# t10_arduino_prog.net
KiCad netlist of a schematic drawn in EAGLE
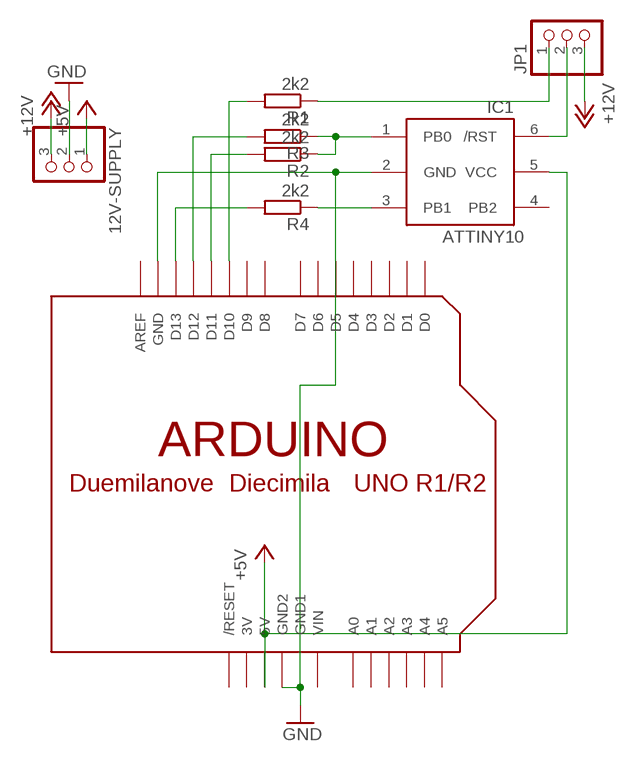
[diagram p0: schematic, sheet 1]

(export (version "E")
  (design (tool "Eeschema 10.0.6"))
  (components
    (comp (ref "12V-SUPPLY")
      (value "PINHD-1X3/90")
      (footprint "eagle-import:1X03_90")
      (libsource (lib "eagle-import") (part "PINHD-1X3/90"))
    )
    (comp (ref "IC1")
      (value "ATTINY10")
      (footprint "eagle-import:SOT23-6")
      (libsource (lib "eagle-import") (part "ATTINY10"))
    )
    (comp (ref "JP1")
      (value "PINHD-1X3")
      (footprint "eagle-import:1X03")
      (libsource (lib "eagle-import") (part "PINHD-1X3"))
    )
    (comp (ref "R1")
      (value "2k2")
      (footprint "eagle-import:0207_2V")
      (libsource (lib "eagle-import") (part "R-EU_0207/2V"))
    )
    (comp (ref "R2")
      (value "2k2")
      (footprint "eagle-import:0207_2V")
      (libsource (lib "eagle-import") (part "R-EU_0207/2V"))
    )
    (comp (ref "R3")
      (value "2k2")
      (footprint "eagle-import:0207_2V")
      (libsource (lib "eagle-import") (part "R-EU_0207/2V"))
    )
    (comp (ref "R4")
      (value "2k2")
      (footprint "eagle-import:0207_2V")
      (libsource (lib "eagle-import") (part "R-EU_0207/2V"))
    )
    (comp (ref "U$1")
      (value "ARDUINO-NOHOLE")
      (footprint "eagle-import:ARDUINO-NOHOLE")
      (libsource (lib "eagle-import") (part "ARDUINO-NOHOLE"))
    )
  )
  (nets
    (net (code "1") (name "+5V") (class "Default")
      (node (ref "12V-SUPPLY") (pin "1") (pinfunction "1_1") (pintype "passive"))
      (node (ref "IC1") (pin "5") (pinfunction "VCC_5") (pintype "power_in"))
      (node (ref "U$1") (pin "5V") (pinfunction "5V_5V") (pintype "power_in"))
    )
    (net (code "2") (name "+12V") (class "Default")
      (node (ref "12V-SUPPLY") (pin "3") (pinfunction "3_3") (pintype "passive"))
      (node (ref "JP1") (pin "3") (pinfunction "3_3") (pintype "passive"))
    )
    (net (code "3") (name "/3V") (class "Default")
      (node (ref "U$1") (pin "3V") (pinfunction "3V_3V") (pintype "power_in"))
    )
    (net (code "4") (name "/VIN") (class "Default")
      (node (ref "U$1") (pin "VIN") (pinfunction "VIN_VIN") (pintype "power_in"))
    )
    (net (code "5") (name "GND") (class "Default")
      (node (ref "12V-SUPPLY") (pin "2") (pinfunction "2_2") (pintype "passive"))
      (node (ref "IC1") (pin "2") (pinfunction "GND_2") (pintype "power_in"))
      (node (ref "U$1") (pin "GND") (pinfunction "GND_GND") (pintype "power_in"))
      (node (ref "U$1") (pin "GND1") (pinfunction "GND1_GND1") (pintype "power_in"))
      (node (ref "U$1") (pin "GND2") (pinfunction "GND2_GND2") (pintype "power_in"))
    )
    (net (code "6") (name "Net-(IC1-PB0)") (class "Default")
      (node (ref "IC1") (pin "1") (pinfunction "PB0_1") (pintype "bidirectional"))
      (node (ref "R2") (pin "1") (pinfunction "1_1") (pintype "passive"))
      (node (ref "R3") (pin "1") (pinfunction "1_1") (pintype "passive"))
    )
    (net (code "7") (name "Net-(IC1-PB1)") (class "Default")
      (node (ref "IC1") (pin "3") (pinfunction "PB1_3") (pintype "bidirectional"))
      (node (ref "R4") (pin "1") (pinfunction "1_1") (pintype "passive"))
    )
    (net (code "8") (name "Net-(IC1-{slash}RST)") (class "Default")
      (node (ref "IC1") (pin "6") (pinfunction "/RST_6") (pintype "bidirectional"))
      (node (ref "JP1") (pin "2") (pinfunction "2_2") (pintype "passive"))
    )
    (net (code "9") (name "Net-(JP1-Pad1)") (class "Default")
      (node (ref "JP1") (pin "1") (pinfunction "1_1") (pintype "passive"))
      (node (ref "R1") (pin "1") (pinfunction "1_1") (pintype "passive"))
    )
    (net (code "10") (name "Net-(R1-Pad2)") (class "Default")
      (node (ref "R1") (pin "2") (pinfunction "2_2") (pintype "passive"))
      (node (ref "U$1") (pin "D10") (pinfunction "D10_D10") (pintype "bidirectional"))
    )
    (net (code "11") (name "Net-(R2-Pad2)") (class "Default")
      (node (ref "R2") (pin "2") (pinfunction "2_2") (pintype "passive"))
      (node (ref "U$1") (pin "D11") (pinfunction "D11_D11") (pintype "bidirectional"))
    )
    (net (code "12") (name "Net-(R3-Pad2)") (class "Default")
      (node (ref "R3") (pin "2") (pinfunction "2_2") (pintype "passive"))
      (node (ref "U$1") (pin "D12") (pinfunction "D12_D12") (pintype "bidirectional"))
    )
    (net (code "13") (name "Net-(R4-Pad2)") (class "Default")
      (node (ref "R4") (pin "2") (pinfunction "2_2") (pintype "passive"))
      (node (ref "U$1") (pin "D13") (pinfunction "D13_D13") (pintype "bidirectional"))
    )
    (net (code "14") (name "unconnected-(IC1-PB2-Pad4)") (class "Default")
      (node (ref "IC1") (pin "4") (pinfunction "PB2_4") (pintype "bidirectional"))
    )
    (net (code "15") (name "unconnected-(U$1-PadA0)") (class "Default")
      (node (ref "U$1") (pin "A0") (pinfunction "A0_A0") (pintype "bidirectional"))
    )
    (net (code "16") (name "unconnected-(U$1-PadA1)") (class "Default")
      (node (ref "U$1") (pin "A1") (pinfunction "A1_A1") (pintype "bidirectional"))
    )
    (net (code "17") (name "unconnected-(U$1-PadA2)") (class "Default")
      (node (ref "U$1") (pin "A2") (pinfunction "A2_A2") (pintype "bidirectional"))
    )
    (net (code "18") (name "unconnected-(U$1-PadA3)") (class "Default")
      (node (ref "U$1") (pin "A3") (pinfunction "A3_A3") (pintype "bidirectional"))
    )
    (net (code "19") (name "unconnected-(U$1-PadA4)") (class "Default")
      (node (ref "U$1") (pin "A4") (pinfunction "A4_A4") (pintype "bidirectional"))
    )
    (net (code "20") (name "unconnected-(U$1-PadA5)") (class "Default")
      (node (ref "U$1") (pin "A5") (pinfunction "A5_A5") (pintype "bidirectional"))
    )
    (net (code "21") (name "unconnected-(U$1-PadAREF)") (class "Default")
      (node (ref "U$1") (pin "AREF") (pinfunction "AREF_AREF") (pintype "bidirectional"))
    )
    (net (code "22") (name "unconnected-(U$1-PadD0)") (class "Default")
      (node (ref "U$1") (pin "D0") (pinfunction "D0_D0") (pintype "bidirectional"))
    )
    (net (code "23") (name "unconnected-(U$1-PadD1)") (class "Default")
      (node (ref "U$1") (pin "D1") (pinfunction "D1_D1") (pintype "bidirectional"))
    )
    (net (code "24") (name "unconnected-(U$1-PadD2)") (class "Default")
      (node (ref "U$1") (pin "D2") (pinfunction "D2_D2") (pintype "bidirectional"))
    )
    (net (code "25") (name "unconnected-(U$1-PadD3)") (class "Default")
      (node (ref "U$1") (pin "D3") (pinfunction "D3_D3") (pintype "bidirectional"))
    )
    (net (code "26") (name "unconnected-(U$1-PadD4)") (class "Default")
      (node (ref "U$1") (pin "D4") (pinfunction "D4_D4") (pintype "bidirectional"))
    )
    (net (code "27") (name "unconnected-(U$1-PadD5)") (class "Default")
      (node (ref "U$1") (pin "D5") (pinfunction "D5_D5") (pintype "bidirectional"))
    )
    (net (code "28") (name "unconnected-(U$1-PadD6)") (class "Default")
      (node (ref "U$1") (pin "D6") (pinfunction "D6_D6") (pintype "bidirectional"))
    )
    (net (code "29") (name "unconnected-(U$1-PadD7)") (class "Default")
      (node (ref "U$1") (pin "D7") (pinfunction "D7_D7") (pintype "bidirectional"))
    )
    (net (code "30") (name "unconnected-(U$1-PadD8)") (class "Default")
      (node (ref "U$1") (pin "D8") (pinfunction "D8_D8") (pintype "bidirectional"))
    )
    (net (code "31") (name "unconnected-(U$1-PadD9)") (class "Default")
      (node (ref "U$1") (pin "D9") (pinfunction "D9_D9") (pintype "bidirectional"))
    )
    (net (code "32") (name "unconnected-(U$1-{slash}RESET-PadRESET)") (class "Default")
      (node (ref "U$1") (pin "RESET") (pinfunction "/RESET_RESET") (pintype "bidirectional"))
    )
  )
)
